# YellowBeanSprout_Sch.net
KiCad netlist of a schematic drawn in Altium Designer
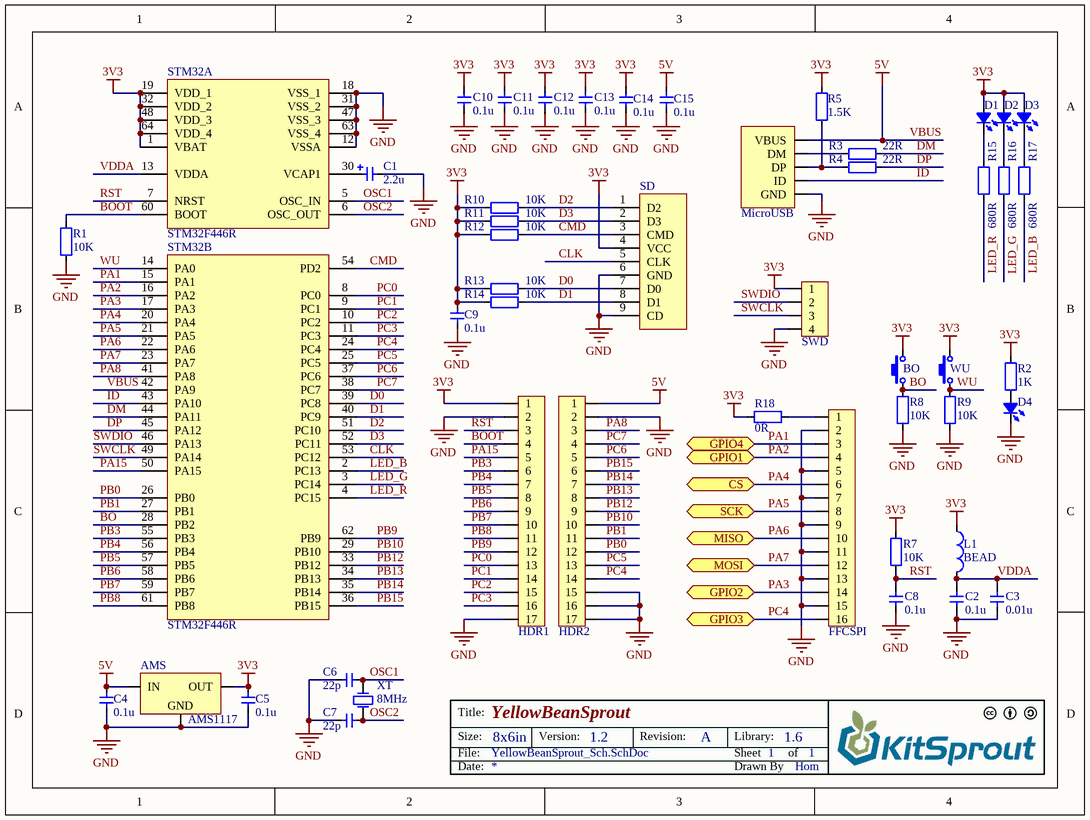
[diagram p0: YellowBeanSprout_Sch.SchDoc]

(export (version "E")
  (design (tool "Eeschema 10.0.6"))
  (components
    (comp (ref "AMS")
      (value "AMS1117")
      (footprint "PCB_IntegratedCircuit:SOT223-3")
      (description "Power")
      (libsource (lib "SCH_IntegratedCircuit") (part "AMS1117"))
    )
    (comp (ref "BO")
      (value "ButtonTACT_3x6x2.5_180")
      (footprint "PCB_Switch:ButtonTACT_3x6x2.5_180")
      (description "Button")
      (libsource (lib "SCH_Switch") (part "ButtonTACT_3x6x2.5_180"))
    )
    (comp (ref "C1")
      (value "2.2u")
      (footprint "PCB_PassiveCap:CAP_TAN_P0805")
      (description "Capacitor")
      (fields (field (name "Comment") "Cap_Tan_0805"))
      (libsource (lib "SCH_Passive") (part "Cap_Tan_0805"))
    )
    (comp (ref "C2")
      (value "0.1u")
      (footprint "PCB_PassiveCap:CAP_0603")
      (description "Capacitor")
      (fields (field (name "Comment") "Cap_0603"))
      (libsource (lib "SCH_Passive") (part "Cap_0603"))
    )
    (comp (ref "C3")
      (value "0.01u")
      (footprint "PCB_PassiveCap:CAP_0603")
      (description "Capacitor")
      (fields (field (name "Comment") "Cap_0603"))
      (libsource (lib "SCH_Passive") (part "Cap_0603"))
    )
    (comp (ref "C4")
      (value "0.1u")
      (footprint "PCB_PassiveCap:CAP_0603")
      (description "Capacitor")
      (fields (field (name "Comment") "Cap_0603"))
      (libsource (lib "SCH_Passive") (part "Cap_0603"))
    )
    (comp (ref "C5")
      (value "0.1u")
      (footprint "PCB_PassiveCap:CAP_0603")
      (description "Capacitor")
      (fields (field (name "Comment") "Cap_0603"))
      (libsource (lib "SCH_Passive") (part "Cap_0603"))
    )
    (comp (ref "C6")
      (value "22p")
      (footprint "PCB_PassiveCap:CAP_0603")
      (description "Capacitor")
      (fields (field (name "Comment") "Cap_0603"))
      (libsource (lib "SCH_Passive") (part "Cap_0603"))
    )
    (comp (ref "C7")
      (value "22p")
      (footprint "PCB_PassiveCap:CAP_0603")
      (description "Capacitor")
      (fields (field (name "Comment") "Cap_0603"))
      (libsource (lib "SCH_Passive") (part "Cap_0603"))
    )
    (comp (ref "C8")
      (value "0.1u")
      (footprint "PCB_PassiveCap:CAP_0603")
      (description "Capacitor")
      (fields (field (name "Comment") "Cap_0603"))
      (libsource (lib "SCH_Passive") (part "Cap_0603"))
    )
    (comp (ref "C9")
      (value "0.1u")
      (footprint "PCB_PassiveCap:CAP_0603")
      (description "Capacitor")
      (fields (field (name "Comment") "Cap_0603"))
      (libsource (lib "SCH_Passive") (part "Cap_0603"))
    )
    (comp (ref "C10")
      (value "0.1u")
      (footprint "PCB_PassiveCap:CAP_0603")
      (description "Capacitor")
      (fields (field (name "Comment") "Cap_0603"))
      (libsource (lib "SCH_Passive") (part "Cap_0603"))
    )
    (comp (ref "C11")
      (value "0.1u")
      (footprint "PCB_PassiveCap:CAP_0603")
      (description "Capacitor")
      (fields (field (name "Comment") "Cap_0603"))
      (libsource (lib "SCH_Passive") (part "Cap_0603"))
    )
    (comp (ref "C12")
      (value "0.1u")
      (footprint "PCB_PassiveCap:CAP_0603")
      (description "Capacitor")
      (fields (field (name "Comment") "Cap_0603"))
      (libsource (lib "SCH_Passive") (part "Cap_0603"))
    )
    (comp (ref "C13")
      (value "0.1u")
      (footprint "PCB_PassiveCap:CAP_0603")
      (description "Capacitor")
      (fields (field (name "Comment") "Cap_0603"))
      (libsource (lib "SCH_Passive") (part "Cap_0603"))
    )
    (comp (ref "C14")
      (value "0.1u")
      (footprint "PCB_PassiveCap:CAP_0603")
      (description "Capacitor")
      (fields (field (name "Comment") "Cap_0603"))
      (libsource (lib "SCH_Passive") (part "Cap_0603"))
    )
    (comp (ref "C15")
      (value "0.1u")
      (footprint "PCB_PassiveCap:CAP_0603")
      (description "Capacitor")
      (fields (field (name "Comment") "Cap_0603"))
      (libsource (lib "SCH_Passive") (part "Cap_0603"))
    )
    (comp (ref "D1")
      (value "LED_0603")
      (footprint "PCB_ActiveLED:LED_0603_RED")
      (description "LED")
      (libsource (lib "SCH_Active") (part "LED_0603"))
    )
    (comp (ref "D2")
      (value "LED_0603")
      (footprint "PCB_ActiveLED:LED_0603_GREEN")
      (description "LED")
      (libsource (lib "SCH_Active") (part "LED_0603"))
    )
    (comp (ref "D3")
      (value "LED_0603")
      (footprint "PCB_ActiveLED:LED_0603_BLUE")
      (description "LED")
      (libsource (lib "SCH_Active") (part "LED_0603"))
    )
    (comp (ref "D4")
      (value "LED_0805")
      (footprint "PCB_ActiveLED:LED_0805_YELLOW")
      (description "LED")
      (libsource (lib "SCH_Active") (part "LED_0805"))
    )
    (comp (ref "FFCSPI")
      (value "FFC_0.5_16")
      (footprint "PCB_ConnectorFFC:FFC_0.5_16")
      (description "FFC")
      (libsource (lib "SCH_Connector") (part "FFC_0.5_16"))
    )
    (comp (ref "HDR1")
      (value "HDR1x17_2.54")
      (footprint "PCB_ConnectorHDR:HDR1X17_2.54_180")
      (description "Header")
      (libsource (lib "SCH_ConnectorHDR") (part "HDR1x17_2.54"))
    )
    (comp (ref "HDR2")
      (value "HDR1x17_2.54T")
      (footprint "PCB_ConnectorHDR:HDR1X17_2.54_180")
      (description "Header")
      (libsource (lib "SCH_ConnectorHDR") (part "HDR1x17_2.54T"))
    )
    (comp (ref "L1")
      (value "BEAD")
      (footprint "PCB_PassiveInd:IND_0603")
      (description "Inductor")
      (fields (field (name "Comment") "Ind_0603"))
      (libsource (lib "SCH_Passive") (part "Ind_0603"))
    )
    (comp (ref "MicroUSB")
      (value "USB_Micro")
      (footprint "PCB_USB:USB_Micro-AB")
      (description "USB")
      (libsource (lib "SCH_USB") (part "USB_Micro"))
    )
    (comp (ref "R1")
      (value "10K")
      (footprint "PCB_PassiveRes:RES_0603")
      (description "Resistor")
      (fields (field (name "Comment") "Res_0603"))
      (libsource (lib "SCH_Passive") (part "Res_0603"))
    )
    (comp (ref "R2")
      (value "1K")
      (footprint "PCB_PassiveRes:RES_0603")
      (description "Resistor")
      (fields (field (name "Comment") "Res_0603"))
      (libsource (lib "SCH_Passive") (part "Res_0603"))
    )
    (comp (ref "R3")
      (value "22R")
      (footprint "PCB_PassiveRes:RES_0603")
      (description "Resistor")
      (fields (field (name "Comment") "Res_0603"))
      (libsource (lib "") (part "Res_0603_1"))
    )
    (comp (ref "R4")
      (value "22R")
      (footprint "PCB_PassiveRes:RES_0603")
      (description "Resistor")
      (fields (field (name "Comment") "Res_0603"))
      (libsource (lib "") (part "Res_0603_1"))
    )
    (comp (ref "R5")
      (value "1.5K")
      (footprint "PCB_PassiveRes:RES_0603")
      (description "Resistor")
      (fields (field (name "Comment") "Res_0603"))
      (libsource (lib "") (part "Res_0603_2"))
    )
    (comp (ref "R7")
      (value "10K")
      (footprint "PCB_PassiveRes:RES_0603")
      (description "Resistor")
      (fields (field (name "Comment") "Res_0603"))
      (libsource (lib "SCH_Passive") (part "Res_0603"))
    )
    (comp (ref "R8")
      (value "10K")
      (footprint "PCB_PassiveRes:RES_0603")
      (description "Resistor")
      (fields (field (name "Comment") "Res_0603"))
      (libsource (lib "SCH_Passive") (part "Res_0603"))
    )
    (comp (ref "R9")
      (value "10K")
      (footprint "PCB_PassiveRes:RES_0603")
      (description "Resistor")
      (fields (field (name "Comment") "Res_0603"))
      (libsource (lib "SCH_Passive") (part "Res_0603"))
    )
    (comp (ref "R10")
      (value "10K")
      (footprint "PCB_PassiveRes:RES_0603")
      (description "Resistor")
      (fields (field (name "Comment") "Res_0603"))
      (libsource (lib "") (part "Res_0603_1"))
    )
    (comp (ref "R11")
      (value "10K")
      (footprint "PCB_PassiveRes:RES_0603")
      (description "Resistor")
      (fields (field (name "Comment") "Res_0603"))
      (libsource (lib "") (part "Res_0603_1"))
    )
    (comp (ref "R12")
      (value "10K")
      (footprint "PCB_PassiveRes:RES_0603")
      (description "Resistor")
      (fields (field (name "Comment") "Res_0603"))
      (libsource (lib "") (part "Res_0603_1"))
    )
    (comp (ref "R13")
      (value "10K")
      (footprint "PCB_PassiveRes:RES_0603")
      (description "Resistor")
      (fields (field (name "Comment") "Res_0603"))
      (libsource (lib "") (part "Res_0603_1"))
    )
    (comp (ref "R14")
      (value "10K")
      (footprint "PCB_PassiveRes:RES_0603")
      (description "Resistor")
      (fields (field (name "Comment") "Res_0603"))
      (libsource (lib "") (part "Res_0603_1"))
    )
    (comp (ref "R15")
      (value "680R")
      (footprint "PCB_PassiveRes:RES_0603")
      (description "Resistor")
      (fields (field (name "Comment") "Res_0603"))
      (libsource (lib "SCH_Passive") (part "Res_0603"))
    )
    (comp (ref "R16")
      (value "680R")
      (footprint "PCB_PassiveRes:RES_0603")
      (description "Resistor")
      (fields (field (name "Comment") "Res_0603"))
      (libsource (lib "SCH_Passive") (part "Res_0603"))
    )
    (comp (ref "R17")
      (value "680R")
      (footprint "PCB_PassiveRes:RES_0603")
      (description "Resistor")
      (fields (field (name "Comment") "Res_0603"))
      (libsource (lib "SCH_Passive") (part "Res_0603"))
    )
    (comp (ref "R18")
      (value "0R")
      (footprint "PCB_PassiveRes:RES_0603")
      (description "Resistor")
      (fields (field (name "Comment") "Res_0603"))
      (libsource (lib "") (part "Res_0603_1"))
    )
    (comp (ref "SD")
      (value "SD_Card_TF")
      (footprint "PCB_SDCard:SD_Card_TF")
      (description "SD")
      (libsource (lib "SCH_SDCard") (part "SD_Card_TF"))
    )
    (comp (ref "STM32")
      (value "STM32F446R")
      (footprint "PCB_IntegratedCircuit:LQFP_P0.5_64")
      (description "MCU")
      (libsource (lib "SCH_IntegratedCircuit") (part "STM32F446R"))
    )
    (comp (ref "SWD")
      (value "HDR1x4_2.54")
      (footprint "PCB_ConnectorHDR:HDR1X4_2.54_90F")
      (description "Header")
      (libsource (lib "SCH_ConnectorHDR") (part "HDR1x4_2.54"))
    )
    (comp (ref "WU")
      (value "ButtonTACT_3x6x2.5_180")
      (footprint "PCB_Switch:ButtonTACT_3x6x2.5_180")
      (description "Button")
      (libsource (lib "SCH_Switch") (part "ButtonTACT_3x6x2.5_180"))
    )
    (comp (ref "XT")
      (value "8MHz")
      (footprint "PCB_Oscillator:XT_5032_2")
      (description "Crystal Oscillator")
      (fields (field (name "Comment") "XTAL_5032_2P"))
      (libsource (lib "SCH_Oscillator") (part "XTAL_5032_2P"))
    )
  )
  (nets
    (net (code "1") (name "/BO") (class "Default")
      (node (ref "BO") (pin "1") (pinfunction "1_1") (pintype "passive"))
      (node (ref "R8") (pin "2") (pinfunction "2_2") (pintype "passive"))
      (node (ref "STM32") (pin "28") (pinfunction "PB2_28") (pintype "passive"))
    )
    (net (code "2") (name "/BOOT") (class "Default")
      (node (ref "HDR1") (pin "4") (pinfunction "4_4") (pintype "passive"))
      (node (ref "R1") (pin "2") (pinfunction "2_2") (pintype "passive"))
      (node (ref "STM32") (pin "60") (pinfunction "BOOT_60") (pintype "passive"))
    )
    (net (code "3") (name "/CLK") (class "Default")
      (node (ref "SD") (pin "5") (pinfunction "CLK_5") (pintype "passive"))
      (node (ref "STM32") (pin "53") (pinfunction "PC12_53") (pintype "passive"))
    )
    (net (code "4") (name "/CMD") (class "Default")
      (node (ref "R12") (pin "1") (pinfunction "1_1") (pintype "passive"))
      (node (ref "SD") (pin "3") (pinfunction "CMD_3") (pintype "passive"))
      (node (ref "STM32") (pin "54") (pinfunction "PD2_54") (pintype "passive"))
    )
    (net (code "5") (name "/D0") (class "Default")
      (node (ref "R13") (pin "1") (pinfunction "1_1") (pintype "passive"))
      (node (ref "SD") (pin "7") (pinfunction "D0_7") (pintype "passive"))
      (node (ref "STM32") (pin "39") (pinfunction "PC8_39") (pintype "passive"))
    )
    (net (code "6") (name "/D1") (class "Default")
      (node (ref "R14") (pin "1") (pinfunction "1_1") (pintype "passive"))
      (node (ref "SD") (pin "8") (pinfunction "D1_8") (pintype "passive"))
      (node (ref "STM32") (pin "40") (pinfunction "PC9_40") (pintype "passive"))
    )
    (net (code "7") (name "/D2") (class "Default")
      (node (ref "R10") (pin "1") (pinfunction "1_1") (pintype "passive"))
      (node (ref "SD") (pin "1") (pinfunction "D2_1") (pintype "passive"))
      (node (ref "STM32") (pin "51") (pinfunction "PC10_51") (pintype "passive"))
    )
    (net (code "8") (name "/D3") (class "Default")
      (node (ref "R11") (pin "1") (pinfunction "1_1") (pintype "passive"))
      (node (ref "SD") (pin "2") (pinfunction "D3_2") (pintype "passive"))
      (node (ref "STM32") (pin "52") (pinfunction "PC11_52") (pintype "passive"))
    )
    (net (code "9") (name "/DM") (class "Default")
      (node (ref "R3") (pin "1") (pinfunction "1_1") (pintype "passive"))
      (node (ref "STM32") (pin "44") (pinfunction "PA11_44") (pintype "passive"))
    )
    (net (code "10") (name "/DP") (class "Default")
      (node (ref "R4") (pin "1") (pinfunction "1_1") (pintype "passive"))
      (node (ref "STM32") (pin "45") (pinfunction "PA12_45") (pintype "passive"))
    )
    (net (code "11") (name "/ID") (class "Default")
      (node (ref "MicroUSB") (pin "4") (pinfunction "ID_4") (pintype "passive"))
      (node (ref "STM32") (pin "43") (pinfunction "PA10_43") (pintype "passive"))
    )
    (net (code "12") (name "/LED_B") (class "Default")
      (node (ref "R17") (pin "1") (pinfunction "1_1") (pintype "passive"))
      (node (ref "STM32") (pin "2") (pinfunction "PC13_2") (pintype "passive"))
    )
    (net (code "13") (name "/LED_G") (class "Default")
      (node (ref "R16") (pin "1") (pinfunction "1_1") (pintype "passive"))
      (node (ref "STM32") (pin "3") (pinfunction "PC14_3") (pintype "passive"))
    )
    (net (code "14") (name "/LED_R") (class "Default")
      (node (ref "R15") (pin "1") (pinfunction "1_1") (pintype "passive"))
      (node (ref "STM32") (pin "4") (pinfunction "PC15_4") (pintype "passive"))
    )
    (net (code "15") (name "/OSC1") (class "Default")
      (node (ref "C6") (pin "1") (pinfunction "1_1") (pintype "passive"))
      (node (ref "STM32") (pin "5") (pinfunction "OSC_IN_5") (pintype "passive"))
      (node (ref "XT") (pin "2") (pinfunction "OSC2_2") (pintype "passive"))
    )
    (net (code "16") (name "/OSC2") (class "Default")
      (node (ref "C7") (pin "1") (pinfunction "1_1") (pintype "passive"))
      (node (ref "STM32") (pin "6") (pinfunction "OSC_OUT_6") (pintype "passive"))
      (node (ref "XT") (pin "1") (pinfunction "OSC1_1") (pintype "passive"))
    )
    (net (code "17") (name "/PA1") (class "Default")
      (node (ref "FFCSPI") (pin "3") (pinfunction "3_3") (pintype "passive"))
      (node (ref "STM32") (pin "15") (pinfunction "PA1_15") (pintype "passive"))
    )
    (net (code "18") (name "/PA2") (class "Default")
      (node (ref "FFCSPI") (pin "4") (pinfunction "4_4") (pintype "passive"))
      (node (ref "STM32") (pin "16") (pinfunction "PA2_16") (pintype "passive"))
    )
    (net (code "19") (name "/PA3") (class "Default")
      (node (ref "FFCSPI") (pin "14") (pinfunction "14_14") (pintype "passive"))
      (node (ref "STM32") (pin "17") (pinfunction "PA3_17") (pintype "passive"))
    )
    (net (code "20") (name "/PA4") (class "Default")
      (node (ref "FFCSPI") (pin "6") (pinfunction "6_6") (pintype "passive"))
      (node (ref "STM32") (pin "20") (pinfunction "PA4_20") (pintype "passive"))
    )
    (net (code "21") (name "/PA5") (class "Default")
      (node (ref "FFCSPI") (pin "8") (pinfunction "8_8") (pintype "passive"))
      (node (ref "STM32") (pin "21") (pinfunction "PA5_21") (pintype "passive"))
    )
    (net (code "22") (name "/PA6") (class "Default")
      (node (ref "FFCSPI") (pin "10") (pinfunction "10_10") (pintype "passive"))
      (node (ref "STM32") (pin "22") (pinfunction "PA6_22") (pintype "passive"))
    )
    (net (code "23") (name "/PA7") (class "Default")
      (node (ref "FFCSPI") (pin "12") (pinfunction "12_12") (pintype "passive"))
      (node (ref "STM32") (pin "23") (pinfunction "PA7_23") (pintype "passive"))
    )
    (net (code "24") (name "/PA8") (class "Default")
      (node (ref "HDR2") (pin "3") (pinfunction "3_3") (pintype "passive"))
      (node (ref "STM32") (pin "41") (pinfunction "PA8_41") (pintype "passive"))
    )
    (net (code "25") (name "/PA15") (class "Default")
      (node (ref "HDR1") (pin "5") (pinfunction "5_5") (pintype "passive"))
      (node (ref "STM32") (pin "50") (pinfunction "PA15_50") (pintype "passive"))
    )
    (net (code "26") (name "/PB0") (class "Default")
      (node (ref "HDR2") (pin "12") (pinfunction "12_12") (pintype "passive"))
      (node (ref "STM32") (pin "26") (pinfunction "PB0_26") (pintype "passive"))
    )
    (net (code "27") (name "/PB1") (class "Default")
      (node (ref "HDR2") (pin "11") (pinfunction "11_11") (pintype "passive"))
      (node (ref "STM32") (pin "27") (pinfunction "PB1_27") (pintype "passive"))
    )
    (net (code "28") (name "/PB3") (class "Default")
      (node (ref "HDR1") (pin "6") (pinfunction "6_6") (pintype "passive"))
      (node (ref "STM32") (pin "55") (pinfunction "PB3_55") (pintype "passive"))
    )
    (net (code "29") (name "/PB4") (class "Default")
      (node (ref "HDR1") (pin "7") (pinfunction "7_7") (pintype "passive"))
      (node (ref "STM32") (pin "56") (pinfunction "PB4_56") (pintype "passive"))
    )
    (net (code "30") (name "/PB5") (class "Default")
      (node (ref "HDR1") (pin "8") (pinfunction "8_8") (pintype "passive"))
      (node (ref "STM32") (pin "57") (pinfunction "PB5_57") (pintype "passive"))
    )
    (net (code "31") (name "/PB6") (class "Default")
      (node (ref "HDR1") (pin "9") (pinfunction "9_9") (pintype "passive"))
      (node (ref "STM32") (pin "58") (pinfunction "PB6_58") (pintype "passive"))
    )
    (net (code "32") (name "/PB7") (class "Default")
      (node (ref "HDR1") (pin "10") (pinfunction "10_10") (pintype "passive"))
      (node (ref "STM32") (pin "59") (pinfunction "PB7_59") (pintype "passive"))
    )
    (net (code "33") (name "/PB8") (class "Default")
      (node (ref "HDR1") (pin "11") (pinfunction "11_11") (pintype "passive"))
      (node (ref "STM32") (pin "61") (pinfunction "PB8_61") (pintype "passive"))
    )
    (net (code "34") (name "/PB9") (class "Default")
      (node (ref "HDR1") (pin "12") (pinfunction "12_12") (pintype "passive"))
      (node (ref "STM32") (pin "62") (pinfunction "PB9_62") (pintype "passive"))
    )
    (net (code "35") (name "/PB10") (class "Default")
      (node (ref "HDR2") (pin "10") (pinfunction "10_10") (pintype "passive"))
      (node (ref "STM32") (pin "29") (pinfunction "PB10_29") (pintype "passive"))
    )
    (net (code "36") (name "/PB12") (class "Default")
      (node (ref "HDR2") (pin "9") (pinfunction "9_9") (pintype "passive"))
      (node (ref "STM32") (pin "33") (pinfunction "PB12_33") (pintype "passive"))
    )
    (net (code "37") (name "/PB13") (class "Default")
      (node (ref "HDR2") (pin "8") (pinfunction "8_8") (pintype "passive"))
      (node (ref "STM32") (pin "34") (pinfunction "PB13_34") (pintype "passive"))
    )
    (net (code "38") (name "/PB14") (class "Default")
      (node (ref "HDR2") (pin "7") (pinfunction "7_7") (pintype "passive"))
      (node (ref "STM32") (pin "35") (pinfunction "PB14_35") (pintype "passive"))
    )
    (net (code "39") (name "/PB15") (class "Default")
      (node (ref "HDR2") (pin "6") (pinfunction "6_6") (pintype "passive"))
      (node (ref "STM32") (pin "36") (pinfunction "PB15_36") (pintype "passive"))
    )
    (net (code "40") (name "/PC0") (class "Default")
      (node (ref "HDR1") (pin "13") (pinfunction "13_13") (pintype "passive"))
      (node (ref "STM32") (pin "8") (pinfunction "PC0_8") (pintype "passive"))
    )
    (net (code "41") (name "/PC1") (class "Default")
      (node (ref "HDR1") (pin "14") (pinfunction "14_14") (pintype "passive"))
      (node (ref "STM32") (pin "9") (pinfunction "PC1_9") (pintype "passive"))
    )
    (net (code "42") (name "/PC2") (class "Default")
      (node (ref "HDR1") (pin "15") (pinfunction "15_15") (pintype "passive"))
      (node (ref "STM32") (pin "10") (pinfunction "PC2_10") (pintype "passive"))
    )
    (net (code "43") (name "/PC3") (class "Default")
      (node (ref "HDR1") (pin "16") (pinfunction "16_16") (pintype "passive"))
      (node (ref "STM32") (pin "11") (pinfunction "PC3_11") (pintype "passive"))
    )
    (net (code "44") (name "/PC4") (class "Default")
      (node (ref "FFCSPI") (pin "16") (pinfunction "16_16") (pintype "passive"))
      (node (ref "HDR2") (pin "14") (pinfunction "14_14") (pintype "passive"))
      (node (ref "STM32") (pin "24") (pinfunction "PC4_24") (pintype "passive"))
    )
    (net (code "45") (name "/PC5") (class "Default")
      (node (ref "HDR2") (pin "13") (pinfunction "13_13") (pintype "passive"))
      (node (ref "STM32") (pin "25") (pinfunction "PC5_25") (pintype "passive"))
    )
    (net (code "46") (name "/PC6") (class "Default")
      (node (ref "HDR2") (pin "5") (pinfunction "5_5") (pintype "passive"))
      (node (ref "STM32") (pin "37") (pinfunction "PC6_37") (pintype "passive"))
    )
    (net (code "47") (name "/PC7") (class "Default")
      (node (ref "HDR2") (pin "4") (pinfunction "4_4") (pintype "passive"))
      (node (ref "STM32") (pin "38") (pinfunction "PC7_38") (pintype "passive"))
    )
    (net (code "48") (name "/RST") (class "Default")
      (node (ref "C8") (pin "2") (pinfunction "2_2") (pintype "passive"))
      (node (ref "HDR1") (pin "3") (pinfunction "3_3") (pintype "passive"))
      (node (ref "R7") (pin "1") (pinfunction "1_1") (pintype "passive"))
      (node (ref "STM32") (pin "7") (pinfunction "NRST_7") (pintype "passive"))
    )
    (net (code "49") (name "/SWCLK") (class "Default")
      (node (ref "STM32") (pin "49") (pinfunction "PA14_49") (pintype "passive"))
      (node (ref "SWD") (pin "3") (pinfunction "3_3") (pintype "passive"))
    )
    (net (code "50") (name "/SWDIO") (class "Default")
      (node (ref "STM32") (pin "46") (pinfunction "PA13_46") (pintype "passive"))
      (node (ref "SWD") (pin "2") (pinfunction "2_2") (pintype "passive"))
    )
    (net (code "51") (name "/VDDA") (class "Default")
      (node (ref "C2") (pin "2") (pinfunction "2_2") (pintype "passive"))
      (node (ref "C3") (pin "2") (pinfunction "2_2") (pintype "passive"))
      (node (ref "L1") (pin "2") (pinfunction "2_2") (pintype "passive"))
      (node (ref "STM32") (pin "13") (pinfunction "VDDA_13") (pintype "passive"))
    )
    (net (code "52") (name "/WU") (class "Default")
      (node (ref "R9") (pin "2") (pinfunction "2_2") (pintype "passive"))
      (node (ref "STM32") (pin "14") (pinfunction "PA0_14") (pintype "passive"))
      (node (ref "WU") (pin "1") (pinfunction "1_1") (pintype "passive"))
    )
    (net (code "53") (name "3V3") (class "Default")
      (node (ref "AMS") (pin "2") (pinfunction "OUT_2") (pintype "power_in"))
      (node (ref "BO") (pin "2") (pinfunction "2_2") (pintype "passive"))
      (node (ref "C10") (pin "2") (pinfunction "2_2") (pintype "passive"))
      (node (ref "C11") (pin "2") (pinfunction "2_2") (pintype "passive"))
      (node (ref "C12") (pin "2") (pinfunction "2_2") (pintype "passive"))
      (node (ref "C13") (pin "2") (pinfunction "2_2") (pintype "passive"))
      (node (ref "C14") (pin "1") (pinfunction "1_1") (pintype "passive"))
      (node (ref "C5") (pin "1") (pinfunction "1_1") (pintype "passive"))
      (node (ref "C9") (pin "1") (pinfunction "1_1") (pintype "passive"))
      (node (ref "D1") (pin "1") (pinfunction "A_1") (pintype "passive"))
      (node (ref "D2") (pin "1") (pinfunction "A_1") (pintype "passive"))
      (node (ref "D3") (pin "1") (pinfunction "A_1") (pintype "passive"))
      (node (ref "HDR1") (pin "1") (pinfunction "1_1") (pintype "passive"))
      (node (ref "L1") (pin "1") (pinfunction "1_1") (pintype "passive"))
      (node (ref "R10") (pin "2") (pinfunction "2_2") (pintype "passive"))
      (node (ref "R11") (pin "2") (pinfunction "2_2") (pintype "passive"))
      (node (ref "R12") (pin "2") (pinfunction "2_2") (pintype "passive"))
      (node (ref "R13") (pin "2") (pinfunction "2_2") (pintype "passive"))
      (node (ref "R14") (pin "2") (pinfunction "2_2") (pintype "passive"))
      (node (ref "R18") (pin "2") (pinfunction "2_2") (pintype "passive"))
      (node (ref "R2") (pin "2") (pinfunction "2_2") (pintype "passive"))
      (node (ref "R5") (pin "1") (pinfunction "1_1") (pintype "passive"))
      (node (ref "R7") (pin "2") (pinfunction "2_2") (pintype "passive"))
      (node (ref "SD") (pin "4") (pinfunction "VCC_4") (pintype "passive"))
      (node (ref "STM32") (pin "1") (pinfunction "VBAT_1") (pintype "passive"))
      (node (ref "STM32") (pin "19") (pinfunction "VDD_1_19") (pintype "passive"))
      (node (ref "STM32") (pin "32") (pinfunction "VDD_2_32") (pintype "passive"))
      (node (ref "STM32") (pin "48") (pinfunction "VDD_3_48") (pintype "passive"))
      (node (ref "STM32") (pin "64") (pinfunction "VDD_4_64") (pintype "passive"))
      (node (ref "SWD") (pin "1") (pinfunction "1_1") (pintype "passive"))
      (node (ref "WU") (pin "2") (pinfunction "2_2") (pintype "passive"))
    )
    (net (code "54") (name "5V") (class "Default")
      (node (ref "AMS") (pin "3") (pinfunction "IN_3") (pintype "power_in"))
      (node (ref "C15") (pin "1") (pinfunction "1_1") (pintype "passive"))
      (node (ref "C4") (pin "1") (pinfunction "1_1") (pintype "passive"))
      (node (ref "HDR2") (pin "1") (pinfunction "1_1") (pintype "passive"))
      (node (ref "MicroUSB") (pin "1") (pinfunction "VBUS_1") (pintype "passive"))
      (node (ref "STM32") (pin "42") (pinfunction "PA9_42") (pintype "passive"))
    )
    (net (code "55") (name "GND") (class "Default")
      (node (ref "AMS") (pin "1") (pinfunction "GND_1") (pintype "power_in"))
      (node (ref "C1") (pin "2") (pinfunction "2_2") (pintype "passive"))
      (node (ref "C10") (pin "1") (pinfunction "1_1") (pintype "passive"))
      (node (ref "C11") (pin "1") (pinfunction "1_1") (pintype "passive"))
      (node (ref "C12") (pin "1") (pinfunction "1_1") (pintype "passive"))
      (node (ref "C13") (pin "1") (pinfunction "1_1") (pintype "passive"))
      (node (ref "C14") (pin "2") (pinfunction "2_2") (pintype "passive"))
      (node (ref "C15") (pin "2") (pinfunction "2_2") (pintype "passive"))
      (node (ref "C2") (pin "1") (pinfunction "1_1") (pintype "passive"))
      (node (ref "C3") (pin "1") (pinfunction "1_1") (pintype "passive"))
      (node (ref "C4") (pin "2") (pinfunction "2_2") (pintype "passive"))
      (node (ref "C5") (pin "2") (pinfunction "2_2") (pintype "passive"))
      (node (ref "C6") (pin "2") (pinfunction "2_2") (pintype "passive"))
      (node (ref "C7") (pin "2") (pinfunction "2_2") (pintype "passive"))
      (node (ref "C8") (pin "1") (pinfunction "1_1") (pintype "passive"))
      (node (ref "C9") (pin "2") (pinfunction "2_2") (pintype "passive"))
      (node (ref "D4") (pin "2") (pinfunction "K_2") (pintype "passive"))
      (node (ref "FFCSPI") (pin "11") (pinfunction "11_11") (pintype "passive"))
      (node (ref "FFCSPI") (pin "13") (pinfunction "13_13") (pintype "passive"))
      (node (ref "FFCSPI") (pin "15") (pinfunction "15_15") (pintype "passive"))
      (node (ref "FFCSPI") (pin "2") (pinfunction "2_2") (pintype "passive"))
      (node (ref "FFCSPI") (pin "5") (pinfunction "5_5") (pintype "passive"))
      (node (ref "FFCSPI") (pin "7") (pinfunction "7_7") (pintype "passive"))
      (node (ref "FFCSPI") (pin "9") (pinfunction "9_9") (pintype "passive"))
      (node (ref "HDR1") (pin "17") (pinfunction "17_17") (pintype "passive"))
      (node (ref "HDR1") (pin "2") (pinfunction "2_2") (pintype "passive"))
      (node (ref "HDR2") (pin "15") (pinfunction "15_15") (pintype "passive"))
      (node (ref "HDR2") (pin "16") (pinfunction "16_16") (pintype "passive"))
      (node (ref "HDR2") (pin "17") (pinfunction "17_17") (pintype "passive"))
      (node (ref "HDR2") (pin "2") (pinfunction "2_2") (pintype "passive"))
      (node (ref "MicroUSB") (pin "5") (pinfunction "GND_5") (pintype "passive"))
      (node (ref "R1") (pin "1") (pinfunction "1_1") (pintype "passive"))
      (node (ref "R8") (pin "1") (pinfunction "1_1") (pintype "passive"))
      (node (ref "R9") (pin "1") (pinfunction "1_1") (pintype "passive"))
      (node (ref "SD") (pin "6") (pinfunction "GND_6") (pintype "passive"))
      (node (ref "SD") (pin "9") (pinfunction "CD_9") (pintype "passive"))
      (node (ref "STM32") (pin "12") (pinfunction "VSSA_12") (pintype "passive"))
      (node (ref "STM32") (pin "18") (pinfunction "VSS_1_18") (pintype "passive"))
      (node (ref "STM32") (pin "31") (pinfunction "VSS_2_31") (pintype "passive"))
      (node (ref "STM32") (pin "47") (pinfunction "VSS_3_47") (pintype "passive"))
      (node (ref "STM32") (pin "63") (pinfunction "VSS_4_63") (pintype "passive"))
      (node (ref "SWD") (pin "4") (pinfunction "4_4") (pintype "passive"))
    )
    (net (code "56") (name "Net-(D1-K)") (class "Default")
      (node (ref "D1") (pin "2") (pinfunction "K_2") (pintype "passive"))
      (node (ref "R15") (pin "2") (pinfunction "2_2") (pintype "passive"))
    )
    (net (code "57") (name "Net-(D2-K)") (class "Default")
      (node (ref "D2") (pin "2") (pinfunction "K_2") (pintype "passive"))
      (node (ref "R16") (pin "2") (pinfunction "2_2") (pintype "passive"))
    )
    (net (code "58") (name "Net-(D3-K)") (class "Default")
      (node (ref "D3") (pin "2") (pinfunction "K_2") (pintype "passive"))
      (node (ref "R17") (pin "2") (pinfunction "2_2") (pintype "passive"))
    )
    (net (code "59") (name "Net-(D4-A)") (class "Default")
      (node (ref "D4") (pin "1") (pinfunction "A_1") (pintype "passive"))
      (node (ref "R2") (pin "1") (pinfunction "1_1") (pintype "passive"))
    )
    (net (code "60") (name "Net-(FFCSPI-Pad1)") (class "Default")
      (node (ref "FFCSPI") (pin "1") (pinfunction "1_1") (pintype "passive"))
      (node (ref "R18") (pin "1") (pinfunction "1_1") (pintype "passive"))
    )
    (net (code "61") (name "Net-(MicroUSB-DM)") (class "Default")
      (node (ref "MicroUSB") (pin "2") (pinfunction "DM_2") (pintype "passive"))
      (node (ref "R3") (pin "2") (pinfunction "2_2") (pintype "passive"))
    )
    (net (code "62") (name "Net-(MicroUSB-DP)") (class "Default")
      (node (ref "MicroUSB") (pin "3") (pinfunction "DP_3") (pintype "passive"))
      (node (ref "R4") (pin "2") (pinfunction "2_2") (pintype "passive"))
      (node (ref "R5") (pin "2") (pinfunction "2_2") (pintype "passive"))
    )
    (net (code "63") (name "Net-(STM32A-VCAP1)") (class "Default")
      (node (ref "C1") (pin "1") (pinfunction "1_1") (pintype "passive"))
      (node (ref "STM32") (pin "30") (pinfunction "VCAP1_30") (pintype "passive"))
    )
  )
)
